# drive_new2.net
KiCad netlist of a schematic drawn in EAGLE
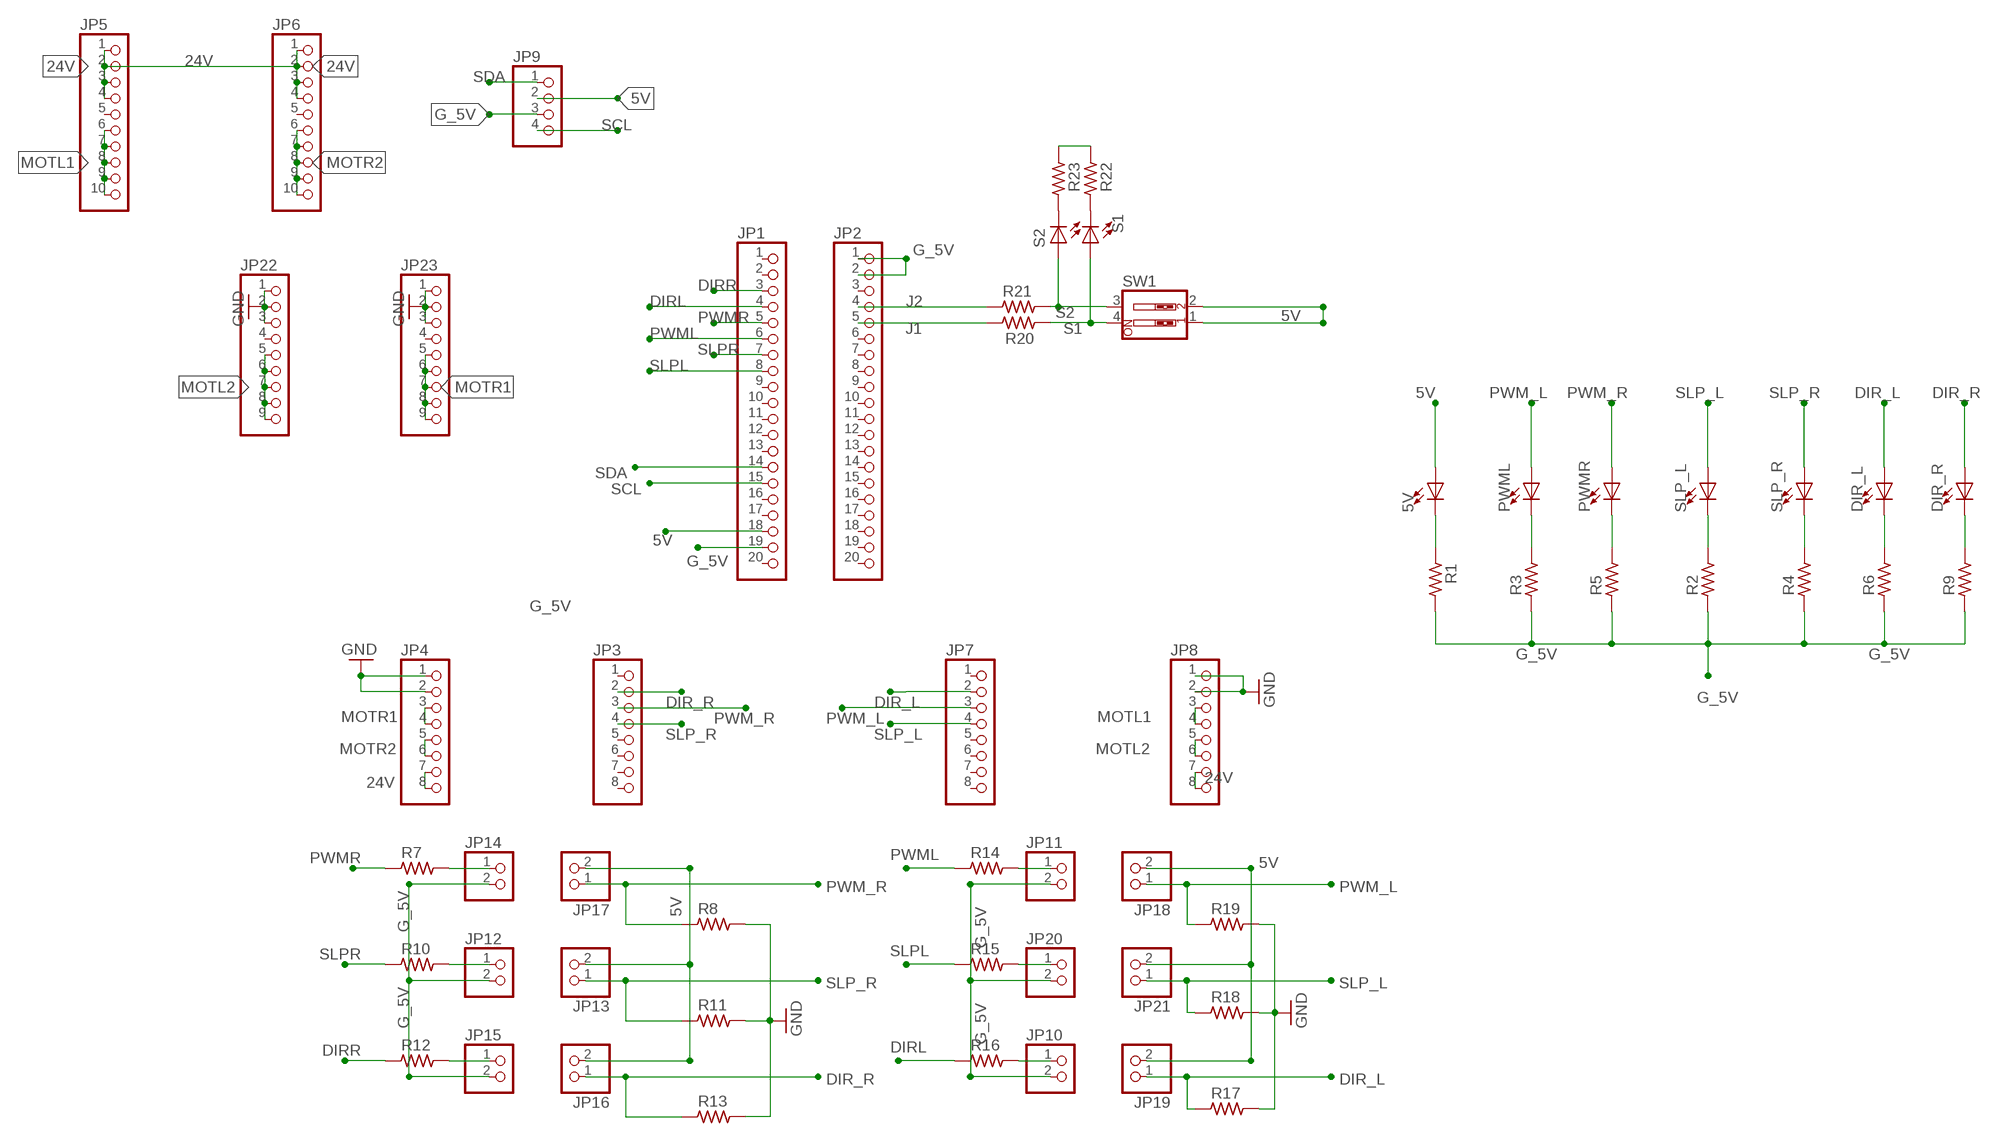
[diagram p0: schematic, sheet 1]

(export (version "E")
  (design (tool "Eeschema 10.0.6"))
  (components
    (comp (ref "5V")
      (value "RED")
      (footprint "eagle-import:LED_1206")
      (libsource (lib "eagle-import") (part "LED_E"))
    )
    (comp (ref "DIR_L")
      (value "BLUE")
      (footprint "eagle-import:LED_1206")
      (libsource (lib "eagle-import") (part "LED_E"))
    )
    (comp (ref "DIR_R")
      (value "BLUE")
      (footprint "eagle-import:LED_1206")
      (libsource (lib "eagle-import") (part "LED_E"))
    )
    (comp (ref "JP1")
      (value "PINHD-1X20")
      (footprint "eagle-import:1X20")
      (libsource (lib "eagle-import") (part "PINHD-1X20"))
    )
    (comp (ref "JP2")
      (value "PINHD-1X20")
      (footprint "eagle-import:1X20")
      (libsource (lib "eagle-import") (part "PINHD-1X20"))
    )
    (comp (ref "JP3")
      (value "PINHD-1X8")
      (footprint "eagle-import:1X08")
      (libsource (lib "eagle-import") (part "PINHD-1X8"))
    )
    (comp (ref "JP4")
      (value "PINHD-1X8")
      (footprint "eagle-import:1X08")
      (libsource (lib "eagle-import") (part "PINHD-1X8"))
    )
    (comp (ref "JP5")
      (value "PINHD-1X10")
      (footprint "eagle-import:1X10")
      (libsource (lib "eagle-import") (part "PINHD-1X10"))
    )
    (comp (ref "JP6")
      (value "PINHD-1X10")
      (footprint "eagle-import:1X10")
      (libsource (lib "eagle-import") (part "PINHD-1X10"))
    )
    (comp (ref "JP7")
      (value "PINHD-1X8")
      (footprint "eagle-import:1X08")
      (libsource (lib "eagle-import") (part "PINHD-1X8"))
    )
    (comp (ref "JP8")
      (value "PINHD-1X8")
      (footprint "eagle-import:1X08")
      (libsource (lib "eagle-import") (part "PINHD-1X8"))
    )
    (comp (ref "JP9")
      (value "PINHD-1X4")
      (footprint "eagle-import:1X04")
      (libsource (lib "eagle-import") (part "PINHD-1X4"))
    )
    (comp (ref "JP10")
      (value "PINHD-1X2")
      (footprint "eagle-import:1X02")
      (libsource (lib "eagle-import") (part "PINHD-1X2"))
    )
    (comp (ref "JP11")
      (value "PINHD-1X2")
      (footprint "eagle-import:1X02")
      (libsource (lib "eagle-import") (part "PINHD-1X2"))
    )
    (comp (ref "JP12")
      (value "PINHD-1X2")
      (footprint "eagle-import:1X02")
      (libsource (lib "eagle-import") (part "PINHD-1X2"))
    )
    (comp (ref "JP13")
      (value "PINHD-1X2")
      (footprint "eagle-import:1X02")
      (libsource (lib "eagle-import") (part "PINHD-1X2"))
    )
    (comp (ref "JP14")
      (value "PINHD-1X2")
      (footprint "eagle-import:1X02")
      (libsource (lib "eagle-import") (part "PINHD-1X2"))
    )
    (comp (ref "JP15")
      (value "PINHD-1X2")
      (footprint "eagle-import:1X02")
      (libsource (lib "eagle-import") (part "PINHD-1X2"))
    )
    (comp (ref "JP16")
      (value "PINHD-1X2")
      (footprint "eagle-import:1X02")
      (libsource (lib "eagle-import") (part "PINHD-1X2"))
    )
    (comp (ref "JP17")
      (value "PINHD-1X2")
      (footprint "eagle-import:1X02")
      (libsource (lib "eagle-import") (part "PINHD-1X2"))
    )
    (comp (ref "JP18")
      (value "PINHD-1X2")
      (footprint "eagle-import:1X02")
      (libsource (lib "eagle-import") (part "PINHD-1X2"))
    )
    (comp (ref "JP19")
      (value "PINHD-1X2")
      (footprint "eagle-import:1X02")
      (libsource (lib "eagle-import") (part "PINHD-1X2"))
    )
    (comp (ref "JP20")
      (value "PINHD-1X2")
      (footprint "eagle-import:1X02")
      (libsource (lib "eagle-import") (part "PINHD-1X2"))
    )
    (comp (ref "JP21")
      (value "PINHD-1X2")
      (footprint "eagle-import:1X02")
      (libsource (lib "eagle-import") (part "PINHD-1X2"))
    )
    (comp (ref "JP22")
      (value "PINHD-1X9")
      (footprint "eagle-import:1X09")
      (libsource (lib "eagle-import") (part "PINHD-1X9"))
    )
    (comp (ref "JP23")
      (value "PINHD-1X9")
      (footprint "eagle-import:1X09")
      (libsource (lib "eagle-import") (part "PINHD-1X9"))
    )
    (comp (ref "PWML")
      (value "RED")
      (footprint "eagle-import:LED_1206")
      (libsource (lib "eagle-import") (part "LED_E"))
    )
    (comp (ref "PWMR")
      (value "RED")
      (footprint "eagle-import:LED_1206")
      (libsource (lib "eagle-import") (part "LED_E"))
    )
    (comp (ref "R1")
      (value "R_0805")
      (footprint "eagle-import:R0805")
      (libsource (lib "eagle-import") (part "R_0805"))
    )
    (comp (ref "R2")
      (value "R_0805")
      (footprint "eagle-import:R0805")
      (libsource (lib "eagle-import") (part "R_0805"))
    )
    (comp (ref "R3")
      (value "R_0805")
      (footprint "eagle-import:R0805")
      (libsource (lib "eagle-import") (part "R_0805"))
    )
    (comp (ref "R4")
      (value "R_0805")
      (footprint "eagle-import:R0805")
      (libsource (lib "eagle-import") (part "R_0805"))
    )
    (comp (ref "R5")
      (value "R_0805")
      (footprint "eagle-import:R0805")
      (libsource (lib "eagle-import") (part "R_0805"))
    )
    (comp (ref "R6")
      (value "R_0805")
      (footprint "eagle-import:R0805")
      (libsource (lib "eagle-import") (part "R_0805"))
    )
    (comp (ref "R7")
      (value "R_0805")
      (footprint "eagle-import:R0805")
      (libsource (lib "eagle-import") (part "R_0805"))
    )
    (comp (ref "R8")
      (value "R_0805")
      (footprint "eagle-import:R0805")
      (libsource (lib "eagle-import") (part "R_0805"))
    )
    (comp (ref "R9")
      (value "R_0805")
      (footprint "eagle-import:R0805")
      (libsource (lib "eagle-import") (part "R_0805"))
    )
    (comp (ref "R10")
      (value "R_0805")
      (footprint "eagle-import:R0805")
      (libsource (lib "eagle-import") (part "R_0805"))
    )
    (comp (ref "R11")
      (value "R_0805")
      (footprint "eagle-import:R0805")
      (libsource (lib "eagle-import") (part "R_0805"))
    )
    (comp (ref "R12")
      (value "R_0805")
      (footprint "eagle-import:R0805")
      (libsource (lib "eagle-import") (part "R_0805"))
    )
    (comp (ref "R13")
      (value "R_0805")
      (footprint "eagle-import:R0805")
      (libsource (lib "eagle-import") (part "R_0805"))
    )
    (comp (ref "R14")
      (value "R_0805")
      (footprint "eagle-import:R0805")
      (libsource (lib "eagle-import") (part "R_0805"))
    )
    (comp (ref "R15")
      (value "R_0805")
      (footprint "eagle-import:R0805")
      (libsource (lib "eagle-import") (part "R_0805"))
    )
    (comp (ref "R16")
      (value "R_0805")
      (footprint "eagle-import:R0805")
      (libsource (lib "eagle-import") (part "R_0805"))
    )
    (comp (ref "R17")
      (value "R_0805")
      (footprint "eagle-import:R0805")
      (libsource (lib "eagle-import") (part "R_0805"))
    )
    (comp (ref "R18")
      (value "R_0805")
      (footprint "eagle-import:R0805")
      (libsource (lib "eagle-import") (part "R_0805"))
    )
    (comp (ref "R19")
      (value "R_0805")
      (footprint "eagle-import:R0805")
      (libsource (lib "eagle-import") (part "R_0805"))
    )
    (comp (ref "R20")
      (value "R_0805")
      (footprint "eagle-import:R0805")
      (libsource (lib "eagle-import") (part "R_0805"))
    )
    (comp (ref "R21")
      (value "R_0805")
      (footprint "eagle-import:R0805")
      (libsource (lib "eagle-import") (part "R_0805"))
    )
    (comp (ref "R22")
      (value "R_0805")
      (footprint "eagle-import:R0805")
      (libsource (lib "eagle-import") (part "R_0805"))
    )
    (comp (ref "R23")
      (value "R_0805")
      (footprint "eagle-import:R0805")
      (libsource (lib "eagle-import") (part "R_0805"))
    )
    (comp (ref "S1")
      (value "RED")
      (footprint "eagle-import:LED_1206")
      (libsource (lib "eagle-import") (part "LED_E"))
    )
    (comp (ref "S2")
      (value "RED")
      (footprint "eagle-import:LED_1206")
      (libsource (lib "eagle-import") (part "LED_E"))
    )
    (comp (ref "SLP_L")
      (value "BLUE")
      (footprint "eagle-import:LED_1206")
      (libsource (lib "eagle-import") (part "LED_E"))
    )
    (comp (ref "SLP_R")
      (value "BLUE")
      (footprint "eagle-import:LED_1206")
      (libsource (lib "eagle-import") (part "LED_E"))
    )
    (comp (ref "SW1")
      (value "SW_DIP-2")
      (footprint "eagle-import:EDG-02")
      (libsource (lib "eagle-import") (part "SW_DIP-2"))
    )
  )
  (nets
    (net (code "1") (name "/DIRL") (class "Default")
      (node (ref "JP1") (pin "4") (pinfunction "4_4") (pintype "passive"))
      (node (ref "R16") (pin "1") (pinfunction "1_1") (pintype "passive"))
    )
    (net (code "2") (name "/DIRR") (class "Default")
      (node (ref "JP1") (pin "3") (pinfunction "3_3") (pintype "passive"))
      (node (ref "R12") (pin "1") (pinfunction "1_1") (pintype "passive"))
    )
    (net (code "3") (name "/DIR_L") (class "Default")
      (node (ref "DIR_L") (pin "A") (pinfunction "A_A") (pintype "passive"))
      (node (ref "JP19") (pin "1") (pinfunction "1_1") (pintype "passive"))
      (node (ref "JP7") (pin "2") (pinfunction "2_2") (pintype "passive"))
      (node (ref "R17") (pin "1") (pinfunction "1_1") (pintype "passive"))
    )
    (net (code "4") (name "/DIR_R") (class "Default")
      (node (ref "DIR_R") (pin "A") (pinfunction "A_A") (pintype "passive"))
      (node (ref "JP16") (pin "1") (pinfunction "1_1") (pintype "passive"))
      (node (ref "JP3") (pin "2") (pinfunction "2_2") (pintype "passive"))
      (node (ref "R13") (pin "1") (pinfunction "1_1") (pintype "passive"))
    )
    (net (code "5") (name "/J1") (class "Default")
      (node (ref "JP2") (pin "5") (pinfunction "5_5") (pintype "passive"))
      (node (ref "R20") (pin "2") (pinfunction "2_2") (pintype "passive"))
    )
    (net (code "6") (name "/J2") (class "Default")
      (node (ref "JP2") (pin "4") (pinfunction "4_4") (pintype "passive"))
      (node (ref "R21") (pin "2") (pinfunction "2_2") (pintype "passive"))
    )
    (net (code "7") (name "/PWML") (class "Default")
      (node (ref "JP1") (pin "6") (pinfunction "6_6") (pintype "passive"))
      (node (ref "R14") (pin "1") (pinfunction "1_1") (pintype "passive"))
    )
    (net (code "8") (name "/PWMR") (class "Default")
      (node (ref "JP1") (pin "5") (pinfunction "5_5") (pintype "passive"))
      (node (ref "R7") (pin "1") (pinfunction "1_1") (pintype "passive"))
    )
    (net (code "9") (name "/PWM_L") (class "Default")
      (node (ref "JP18") (pin "1") (pinfunction "1_1") (pintype "passive"))
      (node (ref "JP7") (pin "3") (pinfunction "3_3") (pintype "passive"))
      (node (ref "PWML") (pin "A") (pinfunction "A_A") (pintype "passive"))
      (node (ref "R19") (pin "1") (pinfunction "1_1") (pintype "passive"))
    )
    (net (code "10") (name "/PWM_R") (class "Default")
      (node (ref "JP17") (pin "1") (pinfunction "1_1") (pintype "passive"))
      (node (ref "JP3") (pin "3") (pinfunction "3_3") (pintype "passive"))
      (node (ref "PWMR") (pin "A") (pinfunction "A_A") (pintype "passive"))
      (node (ref "R8") (pin "1") (pinfunction "1_1") (pintype "passive"))
    )
    (net (code "11") (name "/S1") (class "Default")
      (node (ref "R20") (pin "1") (pinfunction "1_1") (pintype "passive"))
      (node (ref "S1") (pin "A") (pinfunction "A_A") (pintype "passive"))
      (node (ref "SW1") (pin "4") (pinfunction "4_4") (pintype "passive"))
    )
    (net (code "12") (name "/S2") (class "Default")
      (node (ref "R21") (pin "1") (pinfunction "1_1") (pintype "passive"))
      (node (ref "S2") (pin "A") (pinfunction "A_A") (pintype "passive"))
      (node (ref "SW1") (pin "3") (pinfunction "3_3") (pintype "passive"))
    )
    (net (code "13") (name "/SCL") (class "Default")
      (node (ref "JP1") (pin "15") (pinfunction "15_15") (pintype "passive"))
      (node (ref "JP9") (pin "4") (pinfunction "4_4") (pintype "passive"))
    )
    (net (code "14") (name "/SDA") (class "Default")
      (node (ref "JP1") (pin "14") (pinfunction "14_14") (pintype "passive"))
      (node (ref "JP9") (pin "1") (pinfunction "1_1") (pintype "passive"))
    )
    (net (code "15") (name "/SLPL") (class "Default")
      (node (ref "JP1") (pin "8") (pinfunction "8_8") (pintype "passive"))
      (node (ref "R15") (pin "1") (pinfunction "1_1") (pintype "passive"))
    )
    (net (code "16") (name "/SLPR") (class "Default")
      (node (ref "JP1") (pin "7") (pinfunction "7_7") (pintype "passive"))
      (node (ref "R10") (pin "1") (pinfunction "1_1") (pintype "passive"))
    )
    (net (code "17") (name "/SLP_L") (class "Default")
      (node (ref "JP21") (pin "1") (pinfunction "1_1") (pintype "passive"))
      (node (ref "JP7") (pin "4") (pinfunction "4_4") (pintype "passive"))
      (node (ref "R18") (pin "1") (pinfunction "1_1") (pintype "passive"))
      (node (ref "SLP_L") (pin "A") (pinfunction "A_A") (pintype "passive"))
    )
    (net (code "18") (name "/SLP_R") (class "Default")
      (node (ref "JP13") (pin "1") (pinfunction "1_1") (pintype "passive"))
      (node (ref "JP3") (pin "4") (pinfunction "4_4") (pintype "passive"))
      (node (ref "R11") (pin "1") (pinfunction "1_1") (pintype "passive"))
      (node (ref "SLP_R") (pin "A") (pinfunction "A_A") (pintype "passive"))
    )
    (net (code "19") (name "5V") (class "Default")
      (node (ref "5V") (pin "A") (pinfunction "A_A") (pintype "passive"))
      (node (ref "JP1") (pin "18") (pinfunction "18_18") (pintype "passive"))
      (node (ref "JP13") (pin "2") (pinfunction "2_2") (pintype "passive"))
      (node (ref "JP16") (pin "2") (pinfunction "2_2") (pintype "passive"))
      (node (ref "JP17") (pin "2") (pinfunction "2_2") (pintype "passive"))
      (node (ref "JP18") (pin "2") (pinfunction "2_2") (pintype "passive"))
      (node (ref "JP19") (pin "2") (pinfunction "2_2") (pintype "passive"))
      (node (ref "JP21") (pin "2") (pinfunction "2_2") (pintype "passive"))
      (node (ref "JP9") (pin "2") (pinfunction "2_2") (pintype "passive"))
      (node (ref "SW1") (pin "1") (pinfunction "1_1") (pintype "passive"))
      (node (ref "SW1") (pin "2") (pinfunction "2_2") (pintype "passive"))
    )
    (net (code "20") (name "24V") (class "Default")
      (node (ref "JP4") (pin "7") (pinfunction "7_7") (pintype "passive"))
      (node (ref "JP4") (pin "8") (pinfunction "8_8") (pintype "passive"))
      (node (ref "JP5") (pin "1") (pinfunction "1_1") (pintype "passive"))
      (node (ref "JP5") (pin "2") (pinfunction "2_2") (pintype "passive"))
      (node (ref "JP5") (pin "3") (pinfunction "3_3") (pintype "passive"))
      (node (ref "JP5") (pin "4") (pinfunction "4_4") (pintype "passive"))
      (node (ref "JP6") (pin "1") (pinfunction "1_1") (pintype "passive"))
      (node (ref "JP6") (pin "2") (pinfunction "2_2") (pintype "passive"))
      (node (ref "JP6") (pin "3") (pinfunction "3_3") (pintype "passive"))
      (node (ref "JP6") (pin "4") (pinfunction "4_4") (pintype "passive"))
      (node (ref "JP8") (pin "7") (pinfunction "7_7") (pintype "passive"))
      (node (ref "JP8") (pin "8") (pinfunction "8_8") (pintype "passive"))
    )
    (net (code "21") (name "GND") (class "Default")
      (node (ref "JP22") (pin "1") (pinfunction "1_1") (pintype "passive"))
      (node (ref "JP22") (pin "2") (pinfunction "2_2") (pintype "passive"))
      (node (ref "JP22") (pin "3") (pinfunction "3_3") (pintype "passive"))
      (node (ref "JP23") (pin "1") (pinfunction "1_1") (pintype "passive"))
      (node (ref "JP23") (pin "2") (pinfunction "2_2") (pintype "passive"))
      (node (ref "JP23") (pin "3") (pinfunction "3_3") (pintype "passive"))
      (node (ref "JP4") (pin "1") (pinfunction "1_1") (pintype "passive"))
      (node (ref "JP4") (pin "2") (pinfunction "2_2") (pintype "passive"))
      (node (ref "JP8") (pin "1") (pinfunction "1_1") (pintype "passive"))
      (node (ref "JP8") (pin "2") (pinfunction "2_2") (pintype "passive"))
      (node (ref "R11") (pin "2") (pinfunction "2_2") (pintype "passive"))
      (node (ref "R13") (pin "2") (pinfunction "2_2") (pintype "passive"))
      (node (ref "R17") (pin "2") (pinfunction "2_2") (pintype "passive"))
      (node (ref "R18") (pin "2") (pinfunction "2_2") (pintype "passive"))
      (node (ref "R19") (pin "2") (pinfunction "2_2") (pintype "passive"))
      (node (ref "R8") (pin "2") (pinfunction "2_2") (pintype "passive"))
    )
    (net (code "22") (name "G_5V") (class "Default")
      (node (ref "JP1") (pin "19") (pinfunction "19_19") (pintype "passive"))
      (node (ref "JP10") (pin "2") (pinfunction "2_2") (pintype "passive"))
      (node (ref "JP11") (pin "2") (pinfunction "2_2") (pintype "passive"))
      (node (ref "JP12") (pin "2") (pinfunction "2_2") (pintype "passive"))
      (node (ref "JP14") (pin "2") (pinfunction "2_2") (pintype "passive"))
      (node (ref "JP15") (pin "2") (pinfunction "2_2") (pintype "passive"))
      (node (ref "JP2") (pin "1") (pinfunction "1_1") (pintype "passive"))
      (node (ref "JP2") (pin "2") (pinfunction "2_2") (pintype "passive"))
      (node (ref "JP20") (pin "2") (pinfunction "2_2") (pintype "passive"))
      (node (ref "JP9") (pin "3") (pinfunction "3_3") (pintype "passive"))
      (node (ref "R1") (pin "2") (pinfunction "2_2") (pintype "passive"))
      (node (ref "R2") (pin "1") (pinfunction "1_1") (pintype "passive"))
      (node (ref "R22") (pin "1") (pinfunction "1_1") (pintype "passive"))
      (node (ref "R23") (pin "1") (pinfunction "1_1") (pintype "passive"))
      (node (ref "R3") (pin "1") (pinfunction "1_1") (pintype "passive"))
      (node (ref "R4") (pin "1") (pinfunction "1_1") (pintype "passive"))
      (node (ref "R5") (pin "1") (pinfunction "1_1") (pintype "passive"))
      (node (ref "R6") (pin "1") (pinfunction "1_1") (pintype "passive"))
      (node (ref "R9") (pin "1") (pinfunction "1_1") (pintype "passive"))
    )
    (net (code "23") (name "MOTL1") (class "Default")
      (node (ref "JP5") (pin "10") (pinfunction "10_10") (pintype "passive"))
      (node (ref "JP5") (pin "6") (pinfunction "6_6") (pintype "passive"))
      (node (ref "JP5") (pin "7") (pinfunction "7_7") (pintype "passive"))
      (node (ref "JP5") (pin "8") (pinfunction "8_8") (pintype "passive"))
      (node (ref "JP5") (pin "9") (pinfunction "9_9") (pintype "passive"))
      (node (ref "JP8") (pin "3") (pinfunction "3_3") (pintype "passive"))
      (node (ref "JP8") (pin "4") (pinfunction "4_4") (pintype "passive"))
    )
    (net (code "24") (name "MOTL2") (class "Default")
      (node (ref "JP22") (pin "5") (pinfunction "5_5") (pintype "passive"))
      (node (ref "JP22") (pin "6") (pinfunction "6_6") (pintype "passive"))
      (node (ref "JP22") (pin "7") (pinfunction "7_7") (pintype "passive"))
      (node (ref "JP22") (pin "8") (pinfunction "8_8") (pintype "passive"))
      (node (ref "JP22") (pin "9") (pinfunction "9_9") (pintype "passive"))
      (node (ref "JP8") (pin "5") (pinfunction "5_5") (pintype "passive"))
      (node (ref "JP8") (pin "6") (pinfunction "6_6") (pintype "passive"))
    )
    (net (code "25") (name "MOTR1") (class "Default")
      (node (ref "JP23") (pin "5") (pinfunction "5_5") (pintype "passive"))
      (node (ref "JP23") (pin "6") (pinfunction "6_6") (pintype "passive"))
      (node (ref "JP23") (pin "7") (pinfunction "7_7") (pintype "passive"))
      (node (ref "JP23") (pin "8") (pinfunction "8_8") (pintype "passive"))
      (node (ref "JP23") (pin "9") (pinfunction "9_9") (pintype "passive"))
      (node (ref "JP4") (pin "3") (pinfunction "3_3") (pintype "passive"))
      (node (ref "JP4") (pin "4") (pinfunction "4_4") (pintype "passive"))
    )
    (net (code "26") (name "MOTR2") (class "Default")
      (node (ref "JP4") (pin "5") (pinfunction "5_5") (pintype "passive"))
      (node (ref "JP4") (pin "6") (pinfunction "6_6") (pintype "passive"))
      (node (ref "JP6") (pin "10") (pinfunction "10_10") (pintype "passive"))
      (node (ref "JP6") (pin "6") (pinfunction "6_6") (pintype "passive"))
      (node (ref "JP6") (pin "7") (pinfunction "7_7") (pintype "passive"))
      (node (ref "JP6") (pin "8") (pinfunction "8_8") (pintype "passive"))
      (node (ref "JP6") (pin "9") (pinfunction "9_9") (pintype "passive"))
    )
    (net (code "27") (name "Net-(5V-PadC)") (class "Default")
      (node (ref "5V") (pin "C") (pinfunction "C_C") (pintype "passive"))
      (node (ref "R1") (pin "1") (pinfunction "1_1") (pintype "passive"))
    )
    (net (code "28") (name "Net-(DIR_L-PadC)") (class "Default")
      (node (ref "DIR_L") (pin "C") (pinfunction "C_C") (pintype "passive"))
      (node (ref "R6") (pin "2") (pinfunction "2_2") (pintype "passive"))
    )
    (net (code "29") (name "Net-(DIR_R-PadC)") (class "Default")
      (node (ref "DIR_R") (pin "C") (pinfunction "C_C") (pintype "passive"))
      (node (ref "R9") (pin "2") (pinfunction "2_2") (pintype "passive"))
    )
    (net (code "30") (name "Net-(JP10-Pad1)") (class "Default")
      (node (ref "JP10") (pin "1") (pinfunction "1_1") (pintype "passive"))
      (node (ref "R16") (pin "2") (pinfunction "2_2") (pintype "passive"))
    )
    (net (code "31") (name "Net-(JP11-Pad1)") (class "Default")
      (node (ref "JP11") (pin "1") (pinfunction "1_1") (pintype "passive"))
      (node (ref "R14") (pin "2") (pinfunction "2_2") (pintype "passive"))
    )
    (net (code "32") (name "Net-(JP12-Pad1)") (class "Default")
      (node (ref "JP12") (pin "1") (pinfunction "1_1") (pintype "passive"))
      (node (ref "R10") (pin "2") (pinfunction "2_2") (pintype "passive"))
    )
    (net (code "33") (name "Net-(JP14-Pad1)") (class "Default")
      (node (ref "JP14") (pin "1") (pinfunction "1_1") (pintype "passive"))
      (node (ref "R7") (pin "2") (pinfunction "2_2") (pintype "passive"))
    )
    (net (code "34") (name "Net-(JP15-Pad1)") (class "Default")
      (node (ref "JP15") (pin "1") (pinfunction "1_1") (pintype "passive"))
      (node (ref "R12") (pin "2") (pinfunction "2_2") (pintype "passive"))
    )
    (net (code "35") (name "Net-(JP20-Pad1)") (class "Default")
      (node (ref "JP20") (pin "1") (pinfunction "1_1") (pintype "passive"))
      (node (ref "R15") (pin "2") (pinfunction "2_2") (pintype "passive"))
    )
    (net (code "36") (name "Net-(PWML-PadC)") (class "Default")
      (node (ref "PWML") (pin "C") (pinfunction "C_C") (pintype "passive"))
      (node (ref "R3") (pin "2") (pinfunction "2_2") (pintype "passive"))
    )
    (net (code "37") (name "Net-(PWMR-PadC)") (class "Default")
      (node (ref "PWMR") (pin "C") (pinfunction "C_C") (pintype "passive"))
      (node (ref "R5") (pin "2") (pinfunction "2_2") (pintype "passive"))
    )
    (net (code "38") (name "Net-(R2-Pad2)") (class "Default")
      (node (ref "R2") (pin "2") (pinfunction "2_2") (pintype "passive"))
      (node (ref "SLP_L") (pin "C") (pinfunction "C_C") (pintype "passive"))
    )
    (net (code "39") (name "Net-(R4-Pad2)") (class "Default")
      (node (ref "R4") (pin "2") (pinfunction "2_2") (pintype "passive"))
      (node (ref "SLP_R") (pin "C") (pinfunction "C_C") (pintype "passive"))
    )
    (net (code "40") (name "Net-(R22-Pad2)") (class "Default")
      (node (ref "R22") (pin "2") (pinfunction "2_2") (pintype "passive"))
      (node (ref "S1") (pin "C") (pinfunction "C_C") (pintype "passive"))
    )
    (net (code "41") (name "Net-(R23-Pad2)") (class "Default")
      (node (ref "R23") (pin "2") (pinfunction "2_2") (pintype "passive"))
      (node (ref "S2") (pin "C") (pinfunction "C_C") (pintype "passive"))
    )
    (net (code "42") (name "unconnected-(JP1-Pad1)") (class "Default")
      (node (ref "JP1") (pin "1") (pinfunction "1_1") (pintype "passive"))
    )
    (net (code "43") (name "unconnected-(JP1-Pad2)") (class "Default")
      (node (ref "JP1") (pin "2") (pinfunction "2_2") (pintype "passive"))
    )
    (net (code "44") (name "unconnected-(JP1-Pad9)") (class "Default")
      (node (ref "JP1") (pin "9") (pinfunction "9_9") (pintype "passive"))
    )
    (net (code "45") (name "unconnected-(JP1-Pad10)") (class "Default")
      (node (ref "JP1") (pin "10") (pinfunction "10_10") (pintype "passive"))
    )
    (net (code "46") (name "unconnected-(JP1-Pad11)") (class "Default")
      (node (ref "JP1") (pin "11") (pinfunction "11_11") (pintype "passive"))
    )
    (net (code "47") (name "unconnected-(JP1-Pad12)") (class "Default")
      (node (ref "JP1") (pin "12") (pinfunction "12_12") (pintype "passive"))
    )
    (net (code "48") (name "unconnected-(JP1-Pad13)") (class "Default")
      (node (ref "JP1") (pin "13") (pinfunction "13_13") (pintype "passive"))
    )
    (net (code "49") (name "unconnected-(JP1-Pad16)") (class "Default")
      (node (ref "JP1") (pin "16") (pinfunction "16_16") (pintype "passive"))
    )
    (net (code "50") (name "unconnected-(JP1-Pad17)") (class "Default")
      (node (ref "JP1") (pin "17") (pinfunction "17_17") (pintype "passive"))
    )
    (net (code "51") (name "unconnected-(JP1-Pad20)") (class "Default")
      (node (ref "JP1") (pin "20") (pinfunction "20_20") (pintype "passive"))
    )
    (net (code "52") (name "unconnected-(JP2-Pad3)") (class "Default")
      (node (ref "JP2") (pin "3") (pinfunction "3_3") (pintype "passive"))
    )
    (net (code "53") (name "unconnected-(JP2-Pad6)") (class "Default")
      (node (ref "JP2") (pin "6") (pinfunction "6_6") (pintype "passive"))
    )
    (net (code "54") (name "unconnected-(JP2-Pad7)") (class "Default")
      (node (ref "JP2") (pin "7") (pinfunction "7_7") (pintype "passive"))
    )
    (net (code "55") (name "unconnected-(JP2-Pad8)") (class "Default")
      (node (ref "JP2") (pin "8") (pinfunction "8_8") (pintype "passive"))
    )
    (net (code "56") (name "unconnected-(JP2-Pad9)") (class "Default")
      (node (ref "JP2") (pin "9") (pinfunction "9_9") (pintype "passive"))
    )
    (net (code "57") (name "unconnected-(JP2-Pad10)") (class "Default")
      (node (ref "JP2") (pin "10") (pinfunction "10_10") (pintype "passive"))
    )
    (net (code "58") (name "unconnected-(JP2-Pad11)") (class "Default")
      (node (ref "JP2") (pin "11") (pinfunction "11_11") (pintype "passive"))
    )
    (net (code "59") (name "unconnected-(JP2-Pad12)") (class "Default")
      (node (ref "JP2") (pin "12") (pinfunction "12_12") (pintype "passive"))
    )
    (net (code "60") (name "unconnected-(JP2-Pad13)") (class "Default")
      (node (ref "JP2") (pin "13") (pinfunction "13_13") (pintype "passive"))
    )
    (net (code "61") (name "unconnected-(JP2-Pad14)") (class "Default")
      (node (ref "JP2") (pin "14") (pinfunction "14_14") (pintype "passive"))
    )
    (net (code "62") (name "unconnected-(JP2-Pad15)") (class "Default")
      (node (ref "JP2") (pin "15") (pinfunction "15_15") (pintype "passive"))
    )
    (net (code "63") (name "unconnected-(JP2-Pad16)") (class "Default")
      (node (ref "JP2") (pin "16") (pinfunction "16_16") (pintype "passive"))
    )
    (net (code "64") (name "unconnected-(JP2-Pad17)") (class "Default")
      (node (ref "JP2") (pin "17") (pinfunction "17_17") (pintype "passive"))
    )
    (net (code "65") (name "unconnected-(JP2-Pad18)") (class "Default")
      (node (ref "JP2") (pin "18") (pinfunction "18_18") (pintype "passive"))
    )
    (net (code "66") (name "unconnected-(JP2-Pad19)") (class "Default")
      (node (ref "JP2") (pin "19") (pinfunction "19_19") (pintype "passive"))
    )
    (net (code "67") (name "unconnected-(JP2-Pad20)") (class "Default")
      (node (ref "JP2") (pin "20") (pinfunction "20_20") (pintype "passive"))
    )
    (net (code "68") (name "unconnected-(JP3-Pad1)") (class "Default")
      (node (ref "JP3") (pin "1") (pinfunction "1_1") (pintype "passive"))
    )
    (net (code "69") (name "unconnected-(JP3-Pad5)") (class "Default")
      (node (ref "JP3") (pin "5") (pinfunction "5_5") (pintype "passive"))
    )
    (net (code "70") (name "unconnected-(JP3-Pad6)") (class "Default")
      (node (ref "JP3") (pin "6") (pinfunction "6_6") (pintype "passive"))
    )
    (net (code "71") (name "unconnected-(JP3-Pad7)") (class "Default")
      (node (ref "JP3") (pin "7") (pinfunction "7_7") (pintype "passive"))
    )
    (net (code "72") (name "unconnected-(JP3-Pad8)") (class "Default")
      (node (ref "JP3") (pin "8") (pinfunction "8_8") (pintype "passive"))
    )
    (net (code "73") (name "unconnected-(JP5-Pad5)") (class "Default")
      (node (ref "JP5") (pin "5") (pinfunction "5_5") (pintype "passive"))
    )
    (net (code "74") (name "unconnected-(JP6-Pad5)") (class "Default")
      (node (ref "JP6") (pin "5") (pinfunction "5_5") (pintype "passive"))
    )
    (net (code "75") (name "unconnected-(JP7-Pad1)") (class "Default")
      (node (ref "JP7") (pin "1") (pinfunction "1_1") (pintype "passive"))
    )
    (net (code "76") (name "unconnected-(JP7-Pad5)") (class "Default")
      (node (ref "JP7") (pin "5") (pinfunction "5_5") (pintype "passive"))
    )
    (net (code "77") (name "unconnected-(JP7-Pad6)") (class "Default")
      (node (ref "JP7") (pin "6") (pinfunction "6_6") (pintype "passive"))
    )
    (net (code "78") (name "unconnected-(JP7-Pad7)") (class "Default")
      (node (ref "JP7") (pin "7") (pinfunction "7_7") (pintype "passive"))
    )
    (net (code "79") (name "unconnected-(JP7-Pad8)") (class "Default")
      (node (ref "JP7") (pin "8") (pinfunction "8_8") (pintype "passive"))
    )
    (net (code "80") (name "unconnected-(JP22-Pad4)") (class "Default")
      (node (ref "JP22") (pin "4") (pinfunction "4_4") (pintype "passive"))
    )
    (net (code "81") (name "unconnected-(JP23-Pad4)") (class "Default")
      (node (ref "JP23") (pin "4") (pinfunction "4_4") (pintype "passive"))
    )
  )
)
